# mgpcbw02.net
KiCad netlist of a schematic drawn in EAGLE
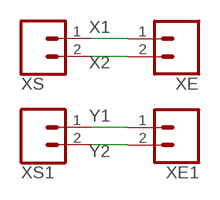
[diagram p0: schematic, sheet 1]

(export (version "E")
  (design (tool "Eeschema 10.0.6"))
  (components
    (comp (ref "XE")
      (value "CONN_021X02_NO_SILK")
      (footprint "eagle-import:1X02_NO_SILK")
      (libsource (lib "eagle-import") (part "CONN_021X02_NO_SILK"))
    )
    (comp (ref "XE1")
      (value "CONN_021X02_NO_SILK")
      (footprint "eagle-import:1X02_NO_SILK")
      (libsource (lib "eagle-import") (part "CONN_021X02_NO_SILK"))
    )
    (comp (ref "XS")
      (value "CONN_021X02_NO_SILK")
      (footprint "eagle-import:1X02_NO_SILK")
      (libsource (lib "eagle-import") (part "CONN_021X02_NO_SILK"))
    )
    (comp (ref "XS1")
      (value "CONN_021X02_NO_SILK")
      (footprint "eagle-import:1X02_NO_SILK")
      (libsource (lib "eagle-import") (part "CONN_021X02_NO_SILK"))
    )
  )
  (nets
    (net (code "1") (name "/X1") (class "Default")
      (node (ref "XE") (pin "1") (pinfunction "1_1") (pintype "passive"))
      (node (ref "XS") (pin "1") (pinfunction "1_1") (pintype "passive"))
    )
    (net (code "2") (name "/X2") (class "Default")
      (node (ref "XE") (pin "2") (pinfunction "2_2") (pintype "passive"))
      (node (ref "XS") (pin "2") (pinfunction "2_2") (pintype "passive"))
    )
    (net (code "3") (name "/Y1") (class "Default")
      (node (ref "XE1") (pin "1") (pinfunction "1_1") (pintype "passive"))
      (node (ref "XS1") (pin "1") (pinfunction "1_1") (pintype "passive"))
    )
    (net (code "4") (name "/Y2") (class "Default")
      (node (ref "XE1") (pin "2") (pinfunction "2_2") (pintype "passive"))
      (node (ref "XS1") (pin "2") (pinfunction "2_2") (pintype "passive"))
    )
  )
)
